# Portable_Lamp_Controller_v2.net
KiCad netlist of a schematic drawn in Altium Designer
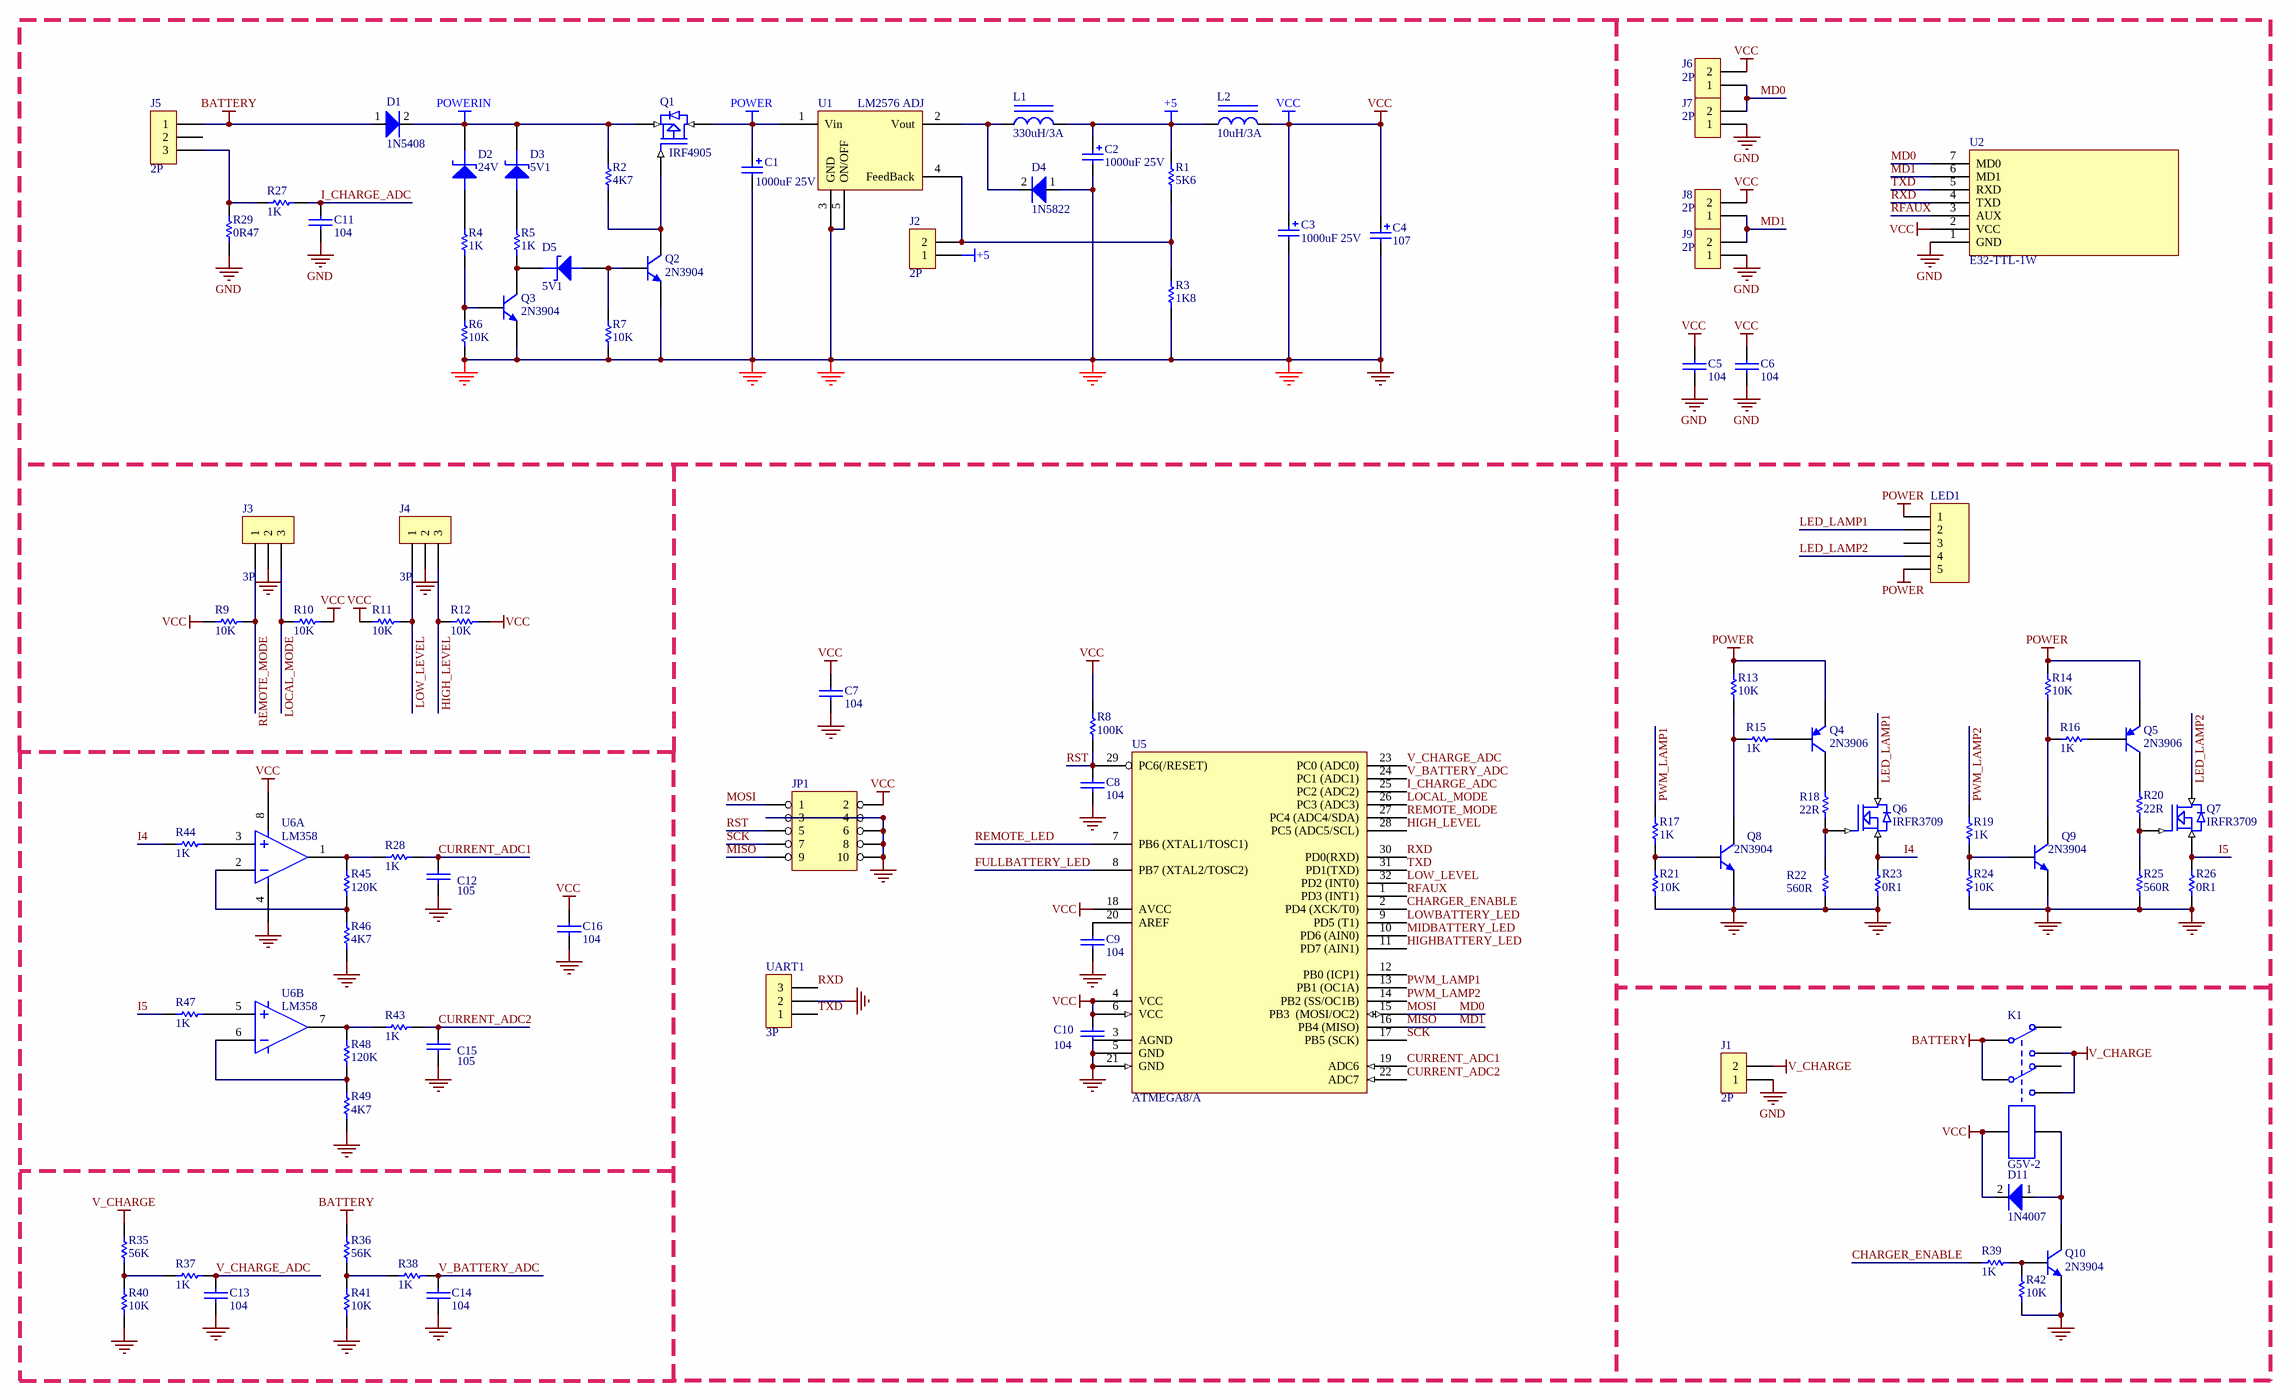
[diagram p0: Portable Lamp Controller v2.SchDoc]

(export (version "E")
  (design (tool "Eeschema 10.0.6"))
  (components
    (comp (ref "C1")
      (value "1000uF 25V")
      (footprint "CAP40x20L")
      (description "Polarized Capacitor (Radial)")
      (fields (field (name "Comment") "Tụ hóa chân cắm1000uF 25V") (field (name "PUBLISHER") "*"))
      (libsource (lib "DnsSchLib") (part "Cap Pol1"))
    )
    (comp (ref "C2")
      (value "1000uF 25V")
      (footprint "CAP40x20L")
      (description "Polarized Capacitor (Radial)")
      (fields (field (name "Comment") "Tụ hóa chân cắm1000uF 25V") (field (name "PUBLISHER") "*"))
      (libsource (lib "DnsSchLib") (part "Cap Pol1"))
    )
    (comp (ref "C3")
      (value "1000uF 25V")
      (footprint "CAP40x20L")
      (description "Polarized Capacitor (Radial)")
      (fields (field (name "Comment") "Tụ hóa chân cắm1000uF 25V") (field (name "PUBLISHER") "*"))
      (libsource (lib "DnsSchLib") (part "Cap Pol1"))
    )
    (comp (ref "C4")
      (value "107")
      (footprint "SMC_E/WA")
      (description "Polarized Capacitor (Radial)")
      (fields (field (name "Comment") "Tụ hóa chân dán107") (field (name "PUBLISHER") "*"))
      (libsource (lib "DnsSchLib") (part "Cap Pol1"))
    )
    (comp (ref "C5")
      (value "104")
      (footprint "0805C")
      (fields (field (name "Comment") "Tụ điện dán 0805104"))
      (libsource (lib "DnsSchLib") (part "CAP"))
    )
    (comp (ref "C6")
      (value "104")
      (footprint "0805C")
      (fields (field (name "Comment") "Tụ điện dán 0805104"))
      (libsource (lib "DnsSchLib") (part "CAP"))
    )
    (comp (ref "C7")
      (value "104")
      (footprint "0805C")
      (fields (field (name "Comment") "Tụ điện dán 0805104"))
      (libsource (lib "DnsSchLib") (part "CAP"))
    )
    (comp (ref "C8")
      (value "104")
      (footprint "0805C")
      (fields (field (name "Comment") "Tụ điện dán 0805104"))
      (libsource (lib "DnsSchLib") (part "CAP"))
    )
    (comp (ref "C9")
      (value "104")
      (footprint "0805C")
      (fields (field (name "Comment") "Tụ điện dán 0805104"))
      (libsource (lib "DnsSchLib") (part "CAP"))
    )
    (comp (ref "C10")
      (value "104")
      (footprint "0805C")
      (fields (field (name "Comment") "Tụ điện dán 0805104"))
      (libsource (lib "DnsSchLib") (part "CAP"))
    )
    (comp (ref "C11")
      (value "104")
      (footprint "0805C")
      (fields (field (name "Comment") "Tụ điện dán 0805104"))
      (libsource (lib "DnsSchLib") (part "CAP"))
    )
    (comp (ref "C12")
      (value "105")
      (footprint "0805C")
      (fields (field (name "Comment") "Tụ điện dán 0805105"))
      (libsource (lib "DnsSchLib") (part "CAP"))
    )
    (comp (ref "C13")
      (value "104")
      (footprint "0805C")
      (fields (field (name "Comment") "Tụ điện dán 0805104"))
      (libsource (lib "DnsSchLib") (part "CAP"))
    )
    (comp (ref "C14")
      (value "104")
      (footprint "0805C")
      (fields (field (name "Comment") "Tụ điện dán 0805104"))
      (libsource (lib "DnsSchLib") (part "CAP"))
    )
    (comp (ref "C15")
      (value "105")
      (footprint "0805C")
      (fields (field (name "Comment") "Tụ điện dán 0805105"))
      (libsource (lib "DnsSchLib") (part "CAP"))
    )
    (comp (ref "C16")
      (value "104")
      (footprint "0805C")
      (fields (field (name "Comment") "Tụ điện dán 0805104"))
      (libsource (lib "DnsSchLib") (part "CAP"))
    )
    (comp (ref "D1")
      (value "1N5408")
      (footprint "1N5408")
      (fields (field (name "Comment") "Diode chỉnh lưu chân cắm 3A1N5408"))
      (libsource (lib "DnsSchLib") (part "DIODE"))
    )
    (comp (ref "D2")
      (value "24V")
      (footprint "1N4148_S")
      (description "Zener Diode")
      (fields (field (name "Comment") "Diode ổn áp zener chân cắm 1W24V"))
      (libsource (lib "DnsSchLib") (part "ZENER2"))
    )
    (comp (ref "D3")
      (value "5V1")
      (footprint "1N4148_S")
      (description "Zener Diode")
      (fields (field (name "Comment") "Diode ổn áp zener chân cắm 1W5V1"))
      (libsource (lib "DnsSchLib") (part "ZENER2"))
    )
    (comp (ref "D4")
      (value "1N5822")
      (footprint "1N5822")
      (fields (field (name "Comment") "Diode xung chân cắm 3A1N5822"))
      (libsource (lib "DnsSchLib") (part "DIODE"))
    )
    (comp (ref "D5")
      (value "5V1")
      (footprint "1N4148_S")
      (description "Zener Diode")
      (fields (field (name "Comment") "Diode ổn áp zener chân cắm 1W5V1"))
      (libsource (lib "DnsSchLib") (part "ZENER2"))
    )
    (comp (ref "D11")
      (value "1N4007")
      (footprint "DIODE1A")
      (fields (field (name "Comment") "Diode chỉnh lưu chân cắm 1A1N4007"))
      (libsource (lib "DnsSchLib") (part "DIODE"))
    )
    (comp (ref "J1")
      (value "2P")
      (footprint "JACK381_2")
      (fields (field (name "Comment") "Giắc xanh loại nằm, 300V/16A - 3.81mm2P"))
      (libsource (lib "DnsSchLib") (part "CON2"))
    )
    (comp (ref "J2")
      (value "2P")
      (footprint "XPAD")
      (fields (field (name "Comment") "Jumper2P"))
      (libsource (lib "DnsSchLib") (part "CON2"))
    )
    (comp (ref "J3")
      (value "3P")
      (footprint "HDR1x3")
      (fields (field (name "Comment") "Jump đực chân thẳng, 2.54mm3P"))
      (libsource (lib "") (part "CON3_1"))
    )
    (comp (ref "J4")
      (value "3P")
      (footprint "HDR1x3")
      (fields (field (name "Comment") "Jump đực chân thẳng, 2.54mm3P"))
      (libsource (lib "") (part "CON3_1"))
    )
    (comp (ref "J5")
      (value "2P")
      (footprint "JACK381_3")
      (fields (field (name "Comment") "Giắc xanh loại nằm, 300V/16A - 3.81mm2P"))
      (libsource (lib "DnsSchLib") (part "CON3"))
    )
    (comp (ref "J6")
      (value "2P")
      (footprint "XPAD")
      (fields (field (name "Comment") "Jumper2P"))
      (libsource (lib "DnsSchLib") (part "CON2"))
    )
    (comp (ref "J7")
      (value "2P")
      (footprint "XPAD")
      (fields (field (name "Comment") "Jumper2P"))
      (libsource (lib "DnsSchLib") (part "CON2"))
    )
    (comp (ref "J8")
      (value "2P")
      (footprint "XPAD")
      (fields (field (name "Comment") "Jumper2P"))
      (libsource (lib "DnsSchLib") (part "CON2"))
    )
    (comp (ref "J9")
      (value "2P")
      (footprint "XPAD")
      (fields (field (name "Comment") "Jumper2P"))
      (libsource (lib "DnsSchLib") (part "CON2"))
    )
    (comp (ref "JP1")
      (value "Jump đực chân thẳng, 2 hàng chân 2.54mm 10P")
      (footprint "HDR2X5")
      (libsource (lib "*") (part "HEADER 5X2"))
    )
    (comp (ref "K1")
      (value "G5V-2")
      (footprint "RELAY")
      (description "Dual-Pole Dual-Throw Relay")
      (fields (field (name "Comment") "Relay OMRON, 8 chân cắmG5V-2") (field (name "PUBLISHER") "*"))
      (libsource (lib "DnsSchLib") (part "Relay-DPDT"))
    )
    (comp (ref "L1")
      (value "330uH/3A")
      (footprint "CAMTRONDUNG")
      (fields (field (name "Comment") "Cuộn cảm chân cắm lõi trụ330uH/3A"))
      (libsource (lib "DnsSchLib") (part "INDUCTORSMALL"))
    )
    (comp (ref "L2")
      (value "10uH/3A")
      (footprint "CAMTRONDUNG")
      (fields (field (name "Comment") "Cuộn cảm chân cắm lõi trụ10uH/3A"))
      (libsource (lib "DnsSchLib") (part "INDUCTORSMALL"))
    )
    (comp (ref "LED1")
      (value "JUMP đực chân thẳng, 2.54mm 5P")
      (footprint "HDR1X5")
      (description "Header, 5-Pin")
      (fields (field (name "PUBLISHER") "Altium Limited"))
      (libsource (lib "Miscellaneous Connectors") (part "Header 5"))
    )
    (comp (ref "Q1")
      (value "IRF4905")
      (footprint "TO220SMD")
      (fields (field (name "Comment") "Transistor trường MOSFET P, chân dán TO-263IRF4905"))
      (libsource (lib "DnsSchLib") (part "MOSFET P"))
    )
    (comp (ref "Q2")
      (value "2N3904")
      (footprint "SOT23S")
      (description "NPN Bipolar Transistor")
      (fields
        (field (name "Comment") "Transistor BJT NPN, chân dán SOT-232N3904")
        (field (name "PUBLISHER") "*")
      )
      (libsource (lib "DnsSchLib") (part "NPN"))
    )
    (comp (ref "Q3")
      (value "2N3904")
      (footprint "SOT23S")
      (description "NPN Bipolar Transistor")
      (fields
        (field (name "Comment") "Transistor BJT NPN, chân dán SOT-232N3904")
        (field (name "PUBLISHER") "*")
      )
      (libsource (lib "DnsSchLib") (part "NPN"))
    )
    (comp (ref "Q4")
      (value "2N3906")
      (footprint "SOT23S")
      (description "PNP Bipolar Transistor")
      (fields
        (field (name "Comment") "Transistor BJT PNP, chân dán SOT-232N3906")
        (field (name "PUBLISHER") "*")
      )
      (libsource (lib "DnsSchLib") (part "PNP"))
    )
    (comp (ref "Q5")
      (value "2N3906")
      (footprint "SOT23S")
      (description "PNP Bipolar Transistor")
      (fields
        (field (name "Comment") "Transistor BJT PNP, chân dán SOT-232N3906")
        (field (name "PUBLISHER") "*")
      )
      (libsource (lib "DnsSchLib") (part "PNP"))
    )
    (comp (ref "Q6")
      (value "IRFR3709")
      (footprint "TO220HSMD")
      (fields (field (name "Comment") "Transistor trường MOSFET N, chân dán TO-263IRFR3709"))
      (libsource (lib "DnsSchLib") (part "MOSFET N"))
    )
    (comp (ref "Q7")
      (value "IRFR3709")
      (footprint "TO220HSMD")
      (fields (field (name "Comment") "Transistor trường MOSFET N, chân dán TO-263IRFR3709"))
      (libsource (lib "DnsSchLib") (part "MOSFET N"))
    )
    (comp (ref "Q8")
      (value "2N3904")
      (footprint "SOT23S")
      (description "NPN Bipolar Transistor")
      (fields
        (field (name "Comment") "Transistor BJT NPN, chân dán SOT-232N3904")
        (field (name "PUBLISHER") "*")
      )
      (libsource (lib "DnsSchLib") (part "NPN"))
    )
    (comp (ref "Q9")
      (value "2N3904")
      (footprint "SOT23S")
      (description "NPN Bipolar Transistor")
      (fields
        (field (name "Comment") "Transistor BJT NPN, chân dán SOT-232N3904")
        (field (name "PUBLISHER") "*")
      )
      (libsource (lib "DnsSchLib") (part "NPN"))
    )
    (comp (ref "Q10")
      (value "2N3904")
      (footprint "SOT23S")
      (description "NPN Bipolar Transistor")
      (fields
        (field (name "Comment") "Transistor BJT NPN, chân dán SOT-232N3904")
        (field (name "PUBLISHER") "*")
      )
      (libsource (lib "DnsSchLib") (part "NPN"))
    )
    (comp (ref "R1")
      (value "5K6")
      (footprint "0805DD")
      (description "Semiconductor Resistor")
      (fields (field (name "Comment") "Điện trở dán 08055K6") (field (name "PUBLISHER") "*"))
      (libsource (lib "DnsSchLib") (part "Res Semi"))
    )
    (comp (ref "R2")
      (value "4K7")
      (footprint "0805DD")
      (description "Semiconductor Resistor")
      (fields (field (name "Comment") "Điện trở dán 08054K7") (field (name "PUBLISHER") "*"))
      (libsource (lib "DnsSchLib") (part "Res Semi"))
    )
    (comp (ref "R3")
      (value "1K8")
      (footprint "0805DD")
      (description "Semiconductor Resistor")
      (fields (field (name "Comment") "Điện trở dán 08051K8") (field (name "PUBLISHER") "*"))
      (libsource (lib "DnsSchLib") (part "Res Semi"))
    )
    (comp (ref "R4")
      (value "1K")
      (footprint "0805DD")
      (description "Semiconductor Resistor")
      (fields (field (name "Comment") "Điện trở dán 08051K") (field (name "PUBLISHER") "*"))
      (libsource (lib "DnsSchLib") (part "Res Semi"))
    )
    (comp (ref "R5")
      (value "1K")
      (footprint "0805DD")
      (description "Semiconductor Resistor")
      (fields (field (name "Comment") "Điện trở dán 08051K") (field (name "PUBLISHER") "*"))
      (libsource (lib "DnsSchLib") (part "Res Semi"))
    )
    (comp (ref "R6")
      (value "10K")
      (footprint "0805DD")
      (description "Semiconductor Resistor")
      (fields (field (name "Comment") "Điện trở dán 080510K") (field (name "PUBLISHER") "*"))
      (libsource (lib "DnsSchLib") (part "Res Semi"))
    )
    (comp (ref "R7")
      (value "10K")
      (footprint "0805DD")
      (description "Semiconductor Resistor")
      (fields (field (name "Comment") "Điện trở dán 080510K") (field (name "PUBLISHER") "*"))
      (libsource (lib "DnsSchLib") (part "Res Semi"))
    )
    (comp (ref "R8")
      (value "100K")
      (footprint "0805DD")
      (description "Semiconductor Resistor")
      (fields (field (name "Comment") "Điện trở dán 0805100K") (field (name "PUBLISHER") "*"))
      (libsource (lib "DnsSchLib") (part "Res Semi"))
    )
    (comp (ref "R9")
      (value "10K")
      (footprint "0805DD")
      (description "Semiconductor Resistor")
      (fields (field (name "Comment") "Điện trở dán 080510K") (field (name "PUBLISHER") "*"))
      (libsource (lib "DnsSchLib") (part "Res Semi"))
    )
    (comp (ref "R10")
      (value "10K")
      (footprint "0805DD")
      (description "Semiconductor Resistor")
      (fields (field (name "Comment") "Điện trở dán 080510K") (field (name "PUBLISHER") "*"))
      (libsource (lib "DnsSchLib") (part "Res Semi"))
    )
    (comp (ref "R11")
      (value "10K")
      (footprint "0805DD")
      (description "Semiconductor Resistor")
      (fields (field (name "Comment") "Điện trở dán 080510K") (field (name "PUBLISHER") "*"))
      (libsource (lib "DnsSchLib") (part "Res Semi"))
    )
    (comp (ref "R12")
      (value "10K")
      (footprint "0805DD")
      (description "Semiconductor Resistor")
      (fields (field (name "Comment") "Điện trở dán 080510K") (field (name "PUBLISHER") "*"))
      (libsource (lib "DnsSchLib") (part "Res Semi"))
    )
    (comp (ref "R13")
      (value "10K")
      (footprint "0805DD")
      (description "Semiconductor Resistor")
      (fields (field (name "Comment") "Điện trở dán 080510K") (field (name "PUBLISHER") "*"))
      (libsource (lib "DnsSchLib") (part "Res Semi"))
    )
    (comp (ref "R14")
      (value "10K")
      (footprint "0805DD")
      (description "Semiconductor Resistor")
      (fields (field (name "Comment") "Điện trở dán 080510K") (field (name "PUBLISHER") "*"))
      (libsource (lib "DnsSchLib") (part "Res Semi"))
    )
    (comp (ref "R15")
      (value "1K")
      (footprint "0805DD")
      (description "Semiconductor Resistor")
      (fields (field (name "Comment") "Điện trở dán 08051K") (field (name "PUBLISHER") "*"))
      (libsource (lib "DnsSchLib") (part "Res Semi"))
    )
    (comp (ref "R16")
      (value "1K")
      (footprint "0805DD")
      (description "Semiconductor Resistor")
      (fields (field (name "Comment") "Điện trở dán 08051K") (field (name "PUBLISHER") "*"))
      (libsource (lib "DnsSchLib") (part "Res Semi"))
    )
    (comp (ref "R17")
      (value "1K")
      (footprint "0805DD")
      (description "Semiconductor Resistor")
      (fields (field (name "Comment") "Điện trở dán 08051K") (field (name "PUBLISHER") "*"))
      (libsource (lib "DnsSchLib") (part "Res Semi"))
    )
    (comp (ref "R18")
      (value "22R")
      (footprint "0805DD")
      (description "Semiconductor Resistor")
      (fields (field (name "Comment") "Điện trở dán 080522R") (field (name "PUBLISHER") "*"))
      (libsource (lib "DnsSchLib") (part "Res Semi"))
    )
    (comp (ref "R19")
      (value "1K")
      (footprint "0805DD")
      (description "Semiconductor Resistor")
      (fields (field (name "Comment") "Điện trở dán 08051K") (field (name "PUBLISHER") "*"))
      (libsource (lib "DnsSchLib") (part "Res Semi"))
    )
    (comp (ref "R20")
      (value "22R")
      (footprint "0805DD")
      (description "Semiconductor Resistor")
      (fields (field (name "Comment") "Điện trở dán 080522R") (field (name "PUBLISHER") "*"))
      (libsource (lib "DnsSchLib") (part "Res Semi"))
    )
    (comp (ref "R21")
      (value "10K")
      (footprint "0805DD")
      (description "Semiconductor Resistor")
      (fields (field (name "Comment") "Điện trở dán 080510K") (field (name "PUBLISHER") "*"))
      (libsource (lib "DnsSchLib") (part "Res Semi"))
    )
    (comp (ref "R22")
      (value "560R")
      (footprint "0805DD")
      (description "Semiconductor Resistor")
      (fields (field (name "Comment") "Điện trở dán 0805560R") (field (name "PUBLISHER") "*"))
      (libsource (lib "DnsSchLib") (part "Res Semi"))
    )
    (comp (ref "R23")
      (value "0R1")
      (footprint "AXIAL0.8S")
      (description "Semiconductor Resistor")
      (fields (field (name "Comment") "Điện trở chân cắm 2W0R1") (field (name "PUBLISHER") "*"))
      (libsource (lib "DnsSchLib") (part "Res Semi"))
    )
    (comp (ref "R24")
      (value "10K")
      (footprint "0805DD")
      (description "Semiconductor Resistor")
      (fields (field (name "Comment") "Điện trở dán 080510K") (field (name "PUBLISHER") "*"))
      (libsource (lib "DnsSchLib") (part "Res Semi"))
    )
    (comp (ref "R25")
      (value "560R")
      (footprint "0805DD")
      (description "Semiconductor Resistor")
      (fields (field (name "Comment") "Điện trở dán 0805560R") (field (name "PUBLISHER") "*"))
      (libsource (lib "DnsSchLib") (part "Res Semi"))
    )
    (comp (ref "R26")
      (value "0R1")
      (footprint "AXIAL0.8S")
      (description "Semiconductor Resistor")
      (fields (field (name "Comment") "Điện trở chân cắm 2W0R1") (field (name "PUBLISHER") "*"))
      (libsource (lib "DnsSchLib") (part "Res Semi"))
    )
    (comp (ref "R27")
      (value "1K")
      (footprint "0805DD")
      (description "Semiconductor Resistor")
      (fields (field (name "Comment") "Điện trở dán 08051K") (field (name "PUBLISHER") "*"))
      (libsource (lib "DnsSchLib") (part "Res Semi"))
    )
    (comp (ref "R28")
      (value "1K")
      (footprint "0805DD")
      (description "Semiconductor Resistor")
      (fields (field (name "Comment") "Điện trở dán 08051K") (field (name "PUBLISHER") "*"))
      (libsource (lib "DnsSchLib") (part "Res Semi"))
    )
    (comp (ref "R29")
      (value "0R47")
      (footprint "AXIAL0.8S")
      (description "Semiconductor Resistor")
      (fields (field (name "Comment") "Điện trở chân cắm 2W0R47") (field (name "PUBLISHER") "*"))
      (libsource (lib "DnsSchLib") (part "Res Semi"))
    )
    (comp (ref "R35")
      (value "56K")
      (footprint "0805DD")
      (description "Semiconductor Resistor")
      (fields (field (name "Comment") "Điện trở dán 0805 1%56K") (field (name "PUBLISHER") "*"))
      (libsource (lib "DnsSchLib") (part "Res Semi"))
    )
    (comp (ref "R36")
      (value "56K")
      (footprint "0805DD")
      (description "Semiconductor Resistor")
      (fields (field (name "Comment") "Điện trở dán 0805 1%56K") (field (name "PUBLISHER") "*"))
      (libsource (lib "DnsSchLib") (part "Res Semi"))
    )
    (comp (ref "R37")
      (value "1K")
      (footprint "0805DD")
      (description "Semiconductor Resistor")
      (fields (field (name "Comment") "Điện trở dán 08051K") (field (name "PUBLISHER") "*"))
      (libsource (lib "DnsSchLib") (part "Res Semi"))
    )
    (comp (ref "R38")
      (value "1K")
      (footprint "0805DD")
      (description "Semiconductor Resistor")
      (fields (field (name "Comment") "Điện trở dán 08051K") (field (name "PUBLISHER") "*"))
      (libsource (lib "DnsSchLib") (part "Res Semi"))
    )
    (comp (ref "R39")
      (value "1K")
      (footprint "0805DD")
      (description "Semiconductor Resistor")
      (fields (field (name "Comment") "Điện trở dán 08051K") (field (name "PUBLISHER") "*"))
      (libsource (lib "DnsSchLib") (part "Res Semi"))
    )
    (comp (ref "R40")
      (value "10K")
      (footprint "0805DD")
      (description "Semiconductor Resistor")
      (fields (field (name "Comment") "Điện trở dán 0805 1%10K") (field (name "PUBLISHER") "*"))
      (libsource (lib "DnsSchLib") (part "Res Semi"))
    )
    (comp (ref "R41")
      (value "10K")
      (footprint "0805DD")
      (description "Semiconductor Resistor")
      (fields (field (name "Comment") "Điện trở dán 0805 1%10K") (field (name "PUBLISHER") "*"))
      (libsource (lib "DnsSchLib") (part "Res Semi"))
    )
    (comp (ref "R42")
      (value "10K")
      (footprint "0805DD")
      (description "Semiconductor Resistor")
      (fields (field (name "Comment") "Điện trở dán 080510K") (field (name "PUBLISHER") "*"))
      (libsource (lib "DnsSchLib") (part "Res Semi"))
    )
    (comp (ref "R43")
      (value "1K")
      (footprint "0805DD")
      (description "Semiconductor Resistor")
      (fields (field (name "Comment") "Điện trở dán 08051K") (field (name "PUBLISHER") "*"))
      (libsource (lib "DnsSchLib") (part "Res Semi"))
    )
    (comp (ref "R44")
      (value "1K")
      (footprint "0805DD")
      (description "Semiconductor Resistor")
      (fields (field (name "Comment") "Điện trở dán 08051K") (field (name "PUBLISHER") "*"))
      (libsource (lib "DnsSchLib") (part "Res Semi"))
    )
    (comp (ref "R45")
      (value "120K")
      (footprint "0805DD")
      (description "Semiconductor Resistor")
      (fields (field (name "Comment") "Điện trở dán 0805 1%120K") (field (name "PUBLISHER") "*"))
      (libsource (lib "DnsSchLib") (part "Res Semi"))
    )
    (comp (ref "R46")
      (value "4K7")
      (footprint "0805DD")
      (description "Semiconductor Resistor")
      (fields (field (name "Comment") "Điện trở dán 0805 1%4K7") (field (name "PUBLISHER") "*"))
      (libsource (lib "DnsSchLib") (part "Res Semi"))
    )
    (comp (ref "R47")
      (value "1K")
      (footprint "0805DD")
      (description "Semiconductor Resistor")
      (fields (field (name "Comment") "Điện trở dán 08051K") (field (name "PUBLISHER") "*"))
      (libsource (lib "DnsSchLib") (part "Res Semi"))
    )
    (comp (ref "R48")
      (value "120K")
      (footprint "0805DD")
      (description "Semiconductor Resistor")
      (fields (field (name "Comment") "Điện trở dán 0805 1%120K") (field (name "PUBLISHER") "*"))
      (libsource (lib "DnsSchLib") (part "Res Semi"))
    )
    (comp (ref "R49")
      (value "4K7")
      (footprint "0805DD")
      (description "Semiconductor Resistor")
      (fields (field (name "Comment") "Điện trở dán 0805 1%4K7") (field (name "PUBLISHER") "*"))
      (libsource (lib "DnsSchLib") (part "Res Semi"))
    )
    (comp (ref "U1")
      (value "LM2576 ADJ")
      (footprint "TO220_5CSMD2")
      (fields (field (name "Comment") "IC chuyển đổi nguồn, chân dánLM2576 ADJ"))
      (libsource (lib "DnsSchLib") (part "LM2576"))
    )
    (comp (ref "U2")
      (value "E32-TTL-1W")
      (footprint "RF_AS32")
      (description "AS32-TTL-1W")
      (fields (field (name "Comment") "Module thu phát không dây RFE32-TTL-1W"))
      (libsource (lib "DnsSchLib") (part "AS32-TTL-1W"))
    )
    (comp (ref "U5")
      (value "ATMEGA8/A")
      (footprint "ATMEGA8")
      (description "TQFP package")
      (fields (field (name "Comment") "Vi điều khiển ATMEL chân dánATMEGA8/A"))
      (libsource (lib "DnsSchLib") (part "ATMEGA8-A"))
    )
    (comp (ref "U6")
      (value "IC khuếch đại thuật toán LM358 chân dán SO-8")
      (footprint "so-8")
      (fields (field (name "NAME") "LM358"))
      (libsource (lib "DnsSchLib") (part "1458"))
    )
    (comp (ref "UART1")
      (value "3P")
      (footprint "HDR1x3")
      (fields (field (name "Comment") "Jump đực chân thẳng, 2.54mm3P"))
      (libsource (lib "") (part "CON3_2"))
    )
  )
  (nets
    (net (code "1") (name "+5") (class "Default")
      (node (ref "C2") (pin "1") (pinfunction "1_1") (pintype "passive"))
      (node (ref "J2") (pin "1") (pinfunction "1_1") (pintype "passive"))
      (node (ref "L1") (pin "2") (pinfunction "2_2") (pintype "passive"))
      (node (ref "L2") (pin "1") (pinfunction "1_1") (pintype "passive"))
      (node (ref "R1") (pin "2") (pinfunction "2_2") (pintype "passive"))
    )
    (net (code "2") (name "/CHARGER_ENABLE") (class "Default")
      (node (ref "R39") (pin "2") (pinfunction "2_2") (pintype "passive"))
      (node (ref "U5") (pin "2") (pinfunction "PD4_(XCK/T0)_2") (pintype "passive"))
    )
    (net (code "3") (name "/CURRENT_ADC1") (class "Default")
      (node (ref "C12") (pin "1") (pinfunction "1_1") (pintype "passive"))
      (node (ref "R28") (pin "1") (pinfunction "1_1") (pintype "passive"))
      (node (ref "U5") (pin "19") (pinfunction "ADC6_19") (pintype "input"))
    )
    (net (code "4") (name "/CURRENT_ADC2") (class "Default")
      (node (ref "C15") (pin "1") (pinfunction "1_1") (pintype "passive"))
      (node (ref "R43") (pin "1") (pinfunction "1_1") (pintype "passive"))
      (node (ref "U5") (pin "22") (pinfunction "ADC7_22") (pintype "input"))
    )
    (net (code "5") (name "/FULLBATTERY_LED") (class "Default")
      (node (ref "U5") (pin "8") (pinfunction "PB7_(XTAL2/TOSC2)_8") (pintype "passive"))
    )
    (net (code "6") (name "/HIGHBATTERY_LED") (class "Default")
      (node (ref "U5") (pin "11") (pinfunction "PD7_(AIN1)_11") (pintype "passive"))
    )
    (net (code "7") (name "/HIGH_LEVEL") (class "Default")
      (node (ref "J4") (pin "3") (pinfunction "3_3") (pintype "passive"))
      (node (ref "R12") (pin "2") (pinfunction "2_2") (pintype "passive"))
      (node (ref "U5") (pin "28") (pinfunction "PC5_(ADC5/SCL)_28") (pintype "passive"))
    )
    (net (code "8") (name "/I4") (class "Default")
      (node (ref "Q6") (pin "3") (pinfunction "S_3") (pintype "input"))
      (node (ref "R23") (pin "2") (pinfunction "2_2") (pintype "passive"))
      (node (ref "R44") (pin "1") (pinfunction "1_1") (pintype "passive"))
    )
    (net (code "9") (name "/I5") (class "Default")
      (node (ref "Q7") (pin "3") (pinfunction "S_3") (pintype "input"))
      (node (ref "R26") (pin "2") (pinfunction "2_2") (pintype "passive"))
      (node (ref "R47") (pin "1") (pinfunction "1_1") (pintype "passive"))
    )
    (net (code "10") (name "/I_CHARGE_ADC") (class "Default")
      (node (ref "C11") (pin "1") (pinfunction "1_1") (pintype "passive"))
      (node (ref "R27") (pin "2") (pinfunction "2_2") (pintype "passive"))
      (node (ref "U5") (pin "25") (pinfunction "PC2_(ADC2)_25") (pintype "passive"))
    )
    (net (code "11") (name "/LED_LAMP1") (class "Default")
      (node (ref "LED1") (pin "2") (pinfunction "2_2") (pintype "passive"))
      (node (ref "Q6") (pin "2") (pinfunction "D_2") (pintype "input"))
    )
    (net (code "12") (name "/LED_LAMP2") (class "Default")
      (node (ref "LED1") (pin "4") (pinfunction "4_4") (pintype "passive"))
      (node (ref "Q7") (pin "2") (pinfunction "D_2") (pintype "input"))
    )
    (net (code "13") (name "/LOCAL_MODE") (class "Default")
      (node (ref "J3") (pin "3") (pinfunction "3_3") (pintype "passive"))
      (node (ref "R10") (pin "1") (pinfunction "1_1") (pintype "passive"))
      (node (ref "U5") (pin "26") (pinfunction "PC3_(ADC3)_26") (pintype "passive"))
    )
    (net (code "14") (name "/LOWBATTERY_LED") (class "Default")
      (node (ref "U5") (pin "9") (pinfunction "PD5_(T1)_9") (pintype "passive"))
    )
    (net (code "15") (name "/LOW_LEVEL") (class "Default")
      (node (ref "J4") (pin "1") (pinfunction "1_1") (pintype "passive"))
      (node (ref "R11") (pin "2") (pinfunction "2_2") (pintype "passive"))
      (node (ref "U5") (pin "32") (pinfunction "PD2_(INT0)_32") (pintype "passive"))
    )
    (net (code "16") (name "/MD0") (class "Default")
      (node (ref "J6") (pin "1") (pinfunction "1_1") (pintype "passive"))
      (node (ref "J7") (pin "2") (pinfunction "2_2") (pintype "passive"))
      (node (ref "JP1") (pin "1") (pinfunction "1_1") (pintype "passive"))
      (node (ref "U2") (pin "7") (pinfunction "MD0_7") (pintype "passive"))
      (node (ref "U5") (pin "15") (pinfunction "PB3__(MOSI/OC2)_15") (pintype "bidirectional"))
    )
    (net (code "17") (name "/MD1") (class "Default")
      (node (ref "J8") (pin "1") (pinfunction "1_1") (pintype "passive"))
      (node (ref "J9") (pin "2") (pinfunction "2_2") (pintype "passive"))
      (node (ref "JP1") (pin "9") (pinfunction "9_9") (pintype "passive"))
      (node (ref "U2") (pin "6") (pinfunction "MD1_6") (pintype "passive"))
      (node (ref "U5") (pin "16") (pinfunction "PB4_(MISO)_16") (pintype "passive"))
    )
    (net (code "18") (name "/MIDBATTERY_LED") (class "Default")
      (node (ref "U5") (pin "10") (pinfunction "PD6_(AIN0)_10") (pintype "passive"))
    )
    (net (code "19") (name "/PWM_LAMP1") (class "Default")
      (node (ref "R17") (pin "1") (pinfunction "1_1") (pintype "passive"))
      (node (ref "U5") (pin "13") (pinfunction "PB1_(OC1A)_13") (pintype "passive"))
    )
    (net (code "20") (name "/PWM_LAMP2") (class "Default")
      (node (ref "R19") (pin "1") (pinfunction "1_1") (pintype "passive"))
      (node (ref "U5") (pin "14") (pinfunction "PB2_(SS/OC1B)_14") (pintype "passive"))
    )
    (net (code "21") (name "/REMOTE_LED") (class "Default")
      (node (ref "U5") (pin "7") (pinfunction "PB6_(XTAL1/TOSC1)_7") (pintype "passive"))
    )
    (net (code "22") (name "/REMOTE_MODE") (class "Default")
      (node (ref "J3") (pin "1") (pinfunction "1_1") (pintype "passive"))
      (node (ref "R9") (pin "1") (pinfunction "1_1") (pintype "passive"))
      (node (ref "U5") (pin "27") (pinfunction "PC4_(ADC4/SDA)_27") (pintype "passive"))
    )
    (net (code "23") (name "/RFAUX") (class "Default")
      (node (ref "U2") (pin "3") (pinfunction "AUX_3") (pintype "passive"))
      (node (ref "U5") (pin "1") (pinfunction "PD3_(INT1)_1") (pintype "passive"))
    )
    (net (code "24") (name "/RST") (class "Default")
      (node (ref "C8") (pin "1") (pinfunction "1_1") (pintype "passive"))
      (node (ref "JP1") (pin "5") (pinfunction "5_5") (pintype "passive"))
      (node (ref "R8") (pin "1") (pinfunction "1_1") (pintype "passive"))
      (node (ref "U5") (pin "29") (pinfunction "PC6(/RESET)_29") (pintype "passive"))
    )
    (net (code "25") (name "/RXD") (class "Default")
      (node (ref "U2") (pin "4") (pinfunction "TXD_4") (pintype "passive"))
      (node (ref "U5") (pin "30") (pinfunction "PD0(RXD)_30") (pintype "passive"))
      (node (ref "UART1") (pin "3") (pinfunction "3_3") (pintype "passive"))
    )
    (net (code "26") (name "/SCK") (class "Default")
      (node (ref "JP1") (pin "7") (pinfunction "7_7") (pintype "passive"))
      (node (ref "U5") (pin "17") (pinfunction "PB5_(SCK)_17") (pintype "passive"))
    )
    (net (code "27") (name "/TXD") (class "Default")
      (node (ref "U2") (pin "5") (pinfunction "RXD_5") (pintype "passive"))
      (node (ref "U5") (pin "31") (pinfunction "PD1(TXD)_31") (pintype "passive"))
      (node (ref "UART1") (pin "1") (pinfunction "1_1") (pintype "passive"))
    )
    (net (code "28") (name "/V_BATTERY_ADC") (class "Default")
      (node (ref "C14") (pin "1") (pinfunction "1_1") (pintype "passive"))
      (node (ref "R38") (pin "2") (pinfunction "2_2") (pintype "passive"))
      (node (ref "U5") (pin "24") (pinfunction "PC1_(ADC1)_24") (pintype "passive"))
    )
    (net (code "29") (name "/V_CHARGE_ADC") (class "Default")
      (node (ref "C13") (pin "1") (pinfunction "1_1") (pintype "passive"))
      (node (ref "R37") (pin "2") (pinfunction "2_2") (pintype "passive"))
      (node (ref "U5") (pin "23") (pinfunction "PC0_(ADC0)_23") (pintype "passive"))
    )
    (net (code "30") (name "BATTERY") (class "Default")
      (node (ref "D1") (pin "1") (pinfunction "A_1") (pintype "passive"))
      (node (ref "J5") (pin "1") (pinfunction "1_1") (pintype "passive"))
      (node (ref "K1") (pin "1") (pinfunction "1_1") (pintype "passive"))
      (node (ref "K1") (pin "4") (pinfunction "4_4") (pintype "passive"))
      (node (ref "R36") (pin "2") (pinfunction "2_2") (pintype "passive"))
    )
    (net (code "31") (name "GND") (class "Default")
      (node (ref "C1") (pin "2") (pinfunction "2_2") (pintype "passive"))
      (node (ref "C10") (pin "1") (pinfunction "1_1") (pintype "passive"))
      (node (ref "C11") (pin "2") (pinfunction "2_2") (pintype "passive"))
      (node (ref "C12") (pin "2") (pinfunction "2_2") (pintype "passive"))
      (node (ref "C13") (pin "2") (pinfunction "2_2") (pintype "passive"))
      (node (ref "C14") (pin "2") (pinfunction "2_2") (pintype "passive"))
      (node (ref "C15") (pin "2") (pinfunction "2_2") (pintype "passive"))
      (node (ref "C16") (pin "1") (pinfunction "1_1") (pintype "passive"))
      (node (ref "C2") (pin "2") (pinfunction "2_2") (pintype "passive"))
      (node (ref "C3") (pin "2") (pinfunction "2_2") (pintype "passive"))
      (node (ref "C4") (pin "2") (pinfunction "2_2") (pintype "passive"))
      (node (ref "C5") (pin "2") (pinfunction "2_2") (pintype "passive"))
      (node (ref "C6") (pin "1") (pinfunction "1_1") (pintype "passive"))
      (node (ref "C7") (pin "1") (pinfunction "1_1") (pintype "passive"))
      (node (ref "C8") (pin "2") (pinfunction "2_2") (pintype "passive"))
      (node (ref "C9") (pin "1") (pinfunction "1_1") (pintype "passive"))
      (node (ref "D4") (pin "1") (pinfunction "A_1") (pintype "passive"))
      (node (ref "J1") (pin "1") (pinfunction "1_1") (pintype "passive"))
      (node (ref "J3") (pin "2") (pinfunction "2_2") (pintype "passive"))
      (node (ref "J4") (pin "2") (pinfunction "2_2") (pintype "passive"))
      (node (ref "J7") (pin "1") (pinfunction "1_1") (pintype "passive"))
      (node (ref "J9") (pin "1") (pinfunction "1_1") (pintype "passive"))
      (node (ref "JP1") (pin "10") (pinfunction "10_10") (pintype "passive"))
      (node (ref "JP1") (pin "3") (pinfunction "3_3") (pintype "passive"))
      (node (ref "JP1") (pin "4") (pinfunction "4_4") (pintype "passive"))
      (node (ref "JP1") (pin "6") (pinfunction "6_6") (pintype "passive"))
      (node (ref "JP1") (pin "8") (pinfunction "8_8") (pintype "passive"))
      (node (ref "Q10") (pin "3") (pinfunction "E_3") (pintype "passive"))
      (node (ref "Q2") (pin "3") (pinfunction "E_3") (pintype "passive"))
      (node (ref "Q3") (pin "3") (pinfunction "E_3") (pintype "passive"))
      (node (ref "Q8") (pin "3") (pinfunction "E_3") (pintype "passive"))
      (node (ref "Q9") (pin "3") (pinfunction "E_3") (pintype "passive"))
      (node (ref "R21") (pin "1") (pinfunction "1_1") (pintype "passive"))
      (node (ref "R22") (pin "2") (pinfunction "2_2") (pintype "passive"))
      (node (ref "R23") (pin "1") (pinfunction "1_1") (pintype "passive"))
      (node (ref "R24") (pin "1") (pinfunction "1_1") (pintype "passive"))
      (node (ref "R25") (pin "2") (pinfunction "2_2") (pintype "passive"))
      (node (ref "R26") (pin "1") (pinfunction "1_1") (pintype "passive"))
      (node (ref "R29") (pin "1") (pinfunction "1_1") (pintype "passive"))
      (node (ref "R3") (pin "1") (pinfunction "1_1") (pintype "passive"))
      (node (ref "R40") (pin "1") (pinfunction "1_1") (pintype "passive"))
      (node (ref "R41") (pin "1") (pinfunction "1_1") (pintype "passive"))
      (node (ref "R42") (pin "1") (pinfunction "1_1") (pintype "passive"))
      (node (ref "R46") (pin "1") (pinfunction "1_1") (pintype "passive"))
      (node (ref "R49") (pin "2") (pinfunction "2_2") (pintype "passive"))
      (node (ref "R6") (pin "1") (pinfunction "1_1") (pintype "passive"))
      (node (ref "R7") (pin "1") (pinfunction "1_1") (pintype "passive"))
      (node (ref "U1") (pin "3") (pinfunction "GND_3") (pintype "passive"))
      (node (ref "U1") (pin "5") (pinfunction "ON/OFF_5") (pintype "passive"))
      (node (ref "U2") (pin "1") (pinfunction "GND_1") (pintype "passive"))
      (node (ref "U5") (pin "21") (pinfunction "GND_21") (pintype "input"))
      (node (ref "U5") (pin "3") (pinfunction "AGND_3") (pintype "passive"))
      (node (ref "U5") (pin "5") (pinfunction "GND_5") (pintype "passive"))
      (node (ref "U6") (pin "4") (pintype "passive"))
      (node (ref "UART1") (pin "2") (pinfunction "2_2") (pintype "passive"))
    )
    (net (code "32") (name "Net-(D2-A)") (class "Default")
      (node (ref "D2") (pin "1") (pinfunction "A_1") (pintype "passive"))
      (node (ref "R4") (pin "2") (pinfunction "2_2") (pintype "passive"))
    )
    (net (code "33") (name "Net-(D3-A)") (class "Default")
      (node (ref "D3") (pin "1") (pinfunction "A_1") (pintype "passive"))
      (node (ref "R5") (pin "2") (pinfunction "2_2") (pintype "passive"))
    )
    (net (code "34") (name "Net-(D4-K)") (class "Default")
      (node (ref "D4") (pin "2") (pinfunction "K_2") (pintype "passive"))
      (node (ref "L1") (pin "1") (pinfunction "1_1") (pintype "passive"))
      (node (ref "U1") (pin "2") (pinfunction "Vout_2") (pintype "passive"))
    )
    (net (code "35") (name "Net-(D5-A)") (class "Default")
      (node (ref "D5") (pin "1") (pinfunction "A_1") (pintype "passive"))
      (node (ref "Q2") (pin "1") (pinfunction "B_1") (pintype "passive"))
      (node (ref "R7") (pin "2") (pinfunction "2_2") (pintype "passive"))
    )
    (net (code "36") (name "Net-(D5-K)") (class "Default")
      (node (ref "D5") (pin "2") (pinfunction "K_2") (pintype "passive"))
      (node (ref "Q3") (pin "2") (pinfunction "C_2") (pintype "passive"))
      (node (ref "R5") (pin "1") (pinfunction "1_1") (pintype "passive"))
    )
    (net (code "37") (name "Net-(D11-A)") (class "Default")
      (node (ref "D11") (pin "1") (pinfunction "A_1") (pintype "passive"))
      (node (ref "K1") (pin "8") (pinfunction "8_8") (pintype "passive"))
      (node (ref "Q10") (pin "2") (pinfunction "C_2") (pintype "passive"))
    )
    (net (code "38") (name "Net-(J5-Pad3)") (class "Default")
      (node (ref "J5") (pin "3") (pinfunction "3_3") (pintype "passive"))
      (node (ref "R27") (pin "1") (pinfunction "1_1") (pintype "passive"))
      (node (ref "R29") (pin "2") (pinfunction "2_2") (pintype "passive"))
    )
    (net (code "39") (name "Net-(Q1-G)") (class "Default")
      (node (ref "Q1") (pin "1") (pinfunction "G_1") (pintype "input"))
      (node (ref "Q2") (pin "2") (pinfunction "C_2") (pintype "passive"))
      (node (ref "R2") (pin "1") (pinfunction "1_1") (pintype "passive"))
    )
    (net (code "40") (name "Net-(Q3-B)") (class "Default")
      (node (ref "Q3") (pin "1") (pinfunction "B_1") (pintype "passive"))
      (node (ref "R4") (pin "1") (pinfunction "1_1") (pintype "passive"))
      (node (ref "R6") (pin "2") (pinfunction "2_2") (pintype "passive"))
    )
    (net (code "41") (name "Net-(Q4-B)") (class "Default")
      (node (ref "Q4") (pin "1") (pinfunction "B_1") (pintype "passive"))
      (node (ref "R15") (pin "1") (pinfunction "1_1") (pintype "passive"))
    )
    (net (code "42") (name "Net-(Q4-C)") (class "Default")
      (node (ref "Q4") (pin "2") (pinfunction "C_2") (pintype "passive"))
      (node (ref "R18") (pin "1") (pinfunction "1_1") (pintype "passive"))
    )
    (net (code "43") (name "Net-(Q5-B)") (class "Default")
      (node (ref "Q5") (pin "1") (pinfunction "B_1") (pintype "passive"))
      (node (ref "R16") (pin "1") (pinfunction "1_1") (pintype "passive"))
    )
    (net (code "44") (name "Net-(Q5-C)") (class "Default")
      (node (ref "Q5") (pin "2") (pinfunction "C_2") (pintype "passive"))
      (node (ref "R20") (pin "1") (pinfunction "1_1") (pintype "passive"))
    )
    (net (code "45") (name "Net-(Q6-G)") (class "Default")
      (node (ref "Q6") (pin "1") (pinfunction "G_1") (pintype "input"))
      (node (ref "R18") (pin "2") (pinfunction "2_2") (pintype "passive"))
      (node (ref "R22") (pin "1") (pinfunction "1_1") (pintype "passive"))
    )
    (net (code "46") (name "Net-(Q7-G)") (class "Default")
      (node (ref "Q7") (pin "1") (pinfunction "G_1") (pintype "input"))
      (node (ref "R20") (pin "2") (pinfunction "2_2") (pintype "passive"))
      (node (ref "R25") (pin "1") (pinfunction "1_1") (pintype "passive"))
    )
    (net (code "47") (name "Net-(Q8-B)") (class "Default")
      (node (ref "Q8") (pin "1") (pinfunction "B_1") (pintype "passive"))
      (node (ref "R17") (pin "2") (pinfunction "2_2") (pintype "passive"))
      (node (ref "R21") (pin "2") (pinfunction "2_2") (pintype "passive"))
    )
    (net (code "48") (name "Net-(Q8-C)") (class "Default")
      (node (ref "Q8") (pin "2") (pinfunction "C_2") (pintype "passive"))
      (node (ref "R13") (pin "1") (pinfunction "1_1") (pintype "passive"))
      (node (ref "R15") (pin "2") (pinfunction "2_2") (pintype "passive"))
    )
    (net (code "49") (name "Net-(Q9-B)") (class "Default")
      (node (ref "Q9") (pin "1") (pinfunction "B_1") (pintype "passive"))
      (node (ref "R19") (pin "2") (pinfunction "2_2") (pintype "passive"))
      (node (ref "R24") (pin "2") (pinfunction "2_2") (pintype "passive"))
    )
    (net (code "50") (name "Net-(Q9-C)") (class "Default")
      (node (ref "Q9") (pin "2") (pinfunction "C_2") (pintype "passive"))
      (node (ref "R14") (pin "1") (pinfunction "1_1") (pintype "passive"))
      (node (ref "R16") (pin "2") (pinfunction "2_2") (pintype "passive"))
    )
    (net (code "51") (name "Net-(Q10-B)") (class "Default")
      (node (ref "Q10") (pin "1") (pinfunction "B_1") (pintype "passive"))
      (node (ref "R39") (pin "1") (pinfunction "1_1") (pintype "passive"))
      (node (ref "R42") (pin "2") (pinfunction "2_2") (pintype "passive"))
    )
    (net (code "52") (name "Net-(R28-Pad2)") (class "Default")
      (node (ref "R28") (pin "2") (pinfunction "2_2") (pintype "passive"))
      (node (ref "R45") (pin "2") (pinfunction "2_2") (pintype "passive"))
      (node (ref "U6") (pin "1") (pintype "passive"))
    )
    (net (code "53") (name "Net-(R35-Pad1)") (class "Default")
      (node (ref "R35") (pin "1") (pinfunction "1_1") (pintype "passive"))
      (node (ref "R37") (pin "1") (pinfunction "1_1") (pintype "passive"))
      (node (ref "R40") (pin "2") (pinfunction "2_2") (pintype "passive"))
    )
    (net (code "54") (name "Net-(R36-Pad1)") (class "Default")
      (node (ref "R36") (pin "1") (pinfunction "1_1") (pintype "passive"))
      (node (ref "R38") (pin "1") (pinfunction "1_1") (pintype "passive"))
      (node (ref "R41") (pin "2") (pinfunction "2_2") (pintype "passive"))
    )
    (net (code "55") (name "Net-(R43-Pad2)") (class "Default")
      (node (ref "R43") (pin "2") (pinfunction "2_2") (pintype "passive"))
      (node (ref "R48") (pin "2") (pinfunction "2_2") (pintype "passive"))
      (node (ref "U6") (pin "7") (pintype "passive"))
    )
    (net (code "56") (name "Net-(R44-Pad2)") (class "Default")
      (node (ref "R44") (pin "2") (pinfunction "2_2") (pintype "passive"))
      (node (ref "U6") (pin "3") (pintype "passive"))
    )
    (net (code "57") (name "Net-(R45-Pad1)") (class "Default")
      (node (ref "R45") (pin "1") (pinfunction "1_1") (pintype "passive"))
      (node (ref "R46") (pin "2") (pinfunction "2_2") (pintype "passive"))
      (node (ref "U6") (pin "2") (pintype "passive"))
    )
    (net (code "58") (name "Net-(R47-Pad2)") (class "Default")
      (node (ref "R47") (pin "2") (pinfunction "2_2") (pintype "passive"))
      (node (ref "U6") (pin "5") (pintype "passive"))
    )
    (net (code "59") (name "Net-(R48-Pad1)") (class "Default")
      (node (ref "R48") (pin "1") (pinfunction "1_1") (pintype "passive"))
      (node (ref "R49") (pin "1") (pinfunction "1_1") (pintype "passive"))
      (node (ref "U6") (pin "6") (pintype "passive"))
    )
    (net (code "60") (name "Net-(U1-FeedBack)") (class "Default")
      (node (ref "J2") (pin "2") (pinfunction "2_2") (pintype "passive"))
      (node (ref "R1") (pin "1") (pinfunction "1_1") (pintype "passive"))
      (node (ref "R3") (pin "2") (pinfunction "2_2") (pintype "passive"))
      (node (ref "U1") (pin "4") (pinfunction "FeedBack_4") (pintype "passive"))
    )
    (net (code "61") (name "Net-(U5-AREF)") (class "Default")
      (node (ref "C9") (pin "2") (pinfunction "2_2") (pintype "passive"))
      (node (ref "U5") (pin "20") (pinfunction "AREF_20") (pintype "passive"))
    )
    (net (code "62") (name "POWER") (class "Default")
      (node (ref "C1") (pin "1") (pinfunction "1_1") (pintype "passive"))
      (node (ref "LED1") (pin "1") (pinfunction "1_1") (pintype "passive"))
      (node (ref "LED1") (pin "5") (pinfunction "5_5") (pintype "passive"))
      (node (ref "Q1") (pin "2") (pinfunction "D_2") (pintype "input"))
      (node (ref "Q4") (pin "3") (pinfunction "E_3") (pintype "passive"))
      (node (ref "Q5") (pin "3") (pinfunction "E_3") (pintype "passive"))
      (node (ref "R13") (pin "2") (pinfunction "2_2") (pintype "passive"))
      (node (ref "R14") (pin "2") (pinfunction "2_2") (pintype "passive"))
      (node (ref "U1") (pin "1") (pinfunction "Vin_1") (pintype "passive"))
    )
    (net (code "63") (name "POWERIN") (class "Default")
      (node (ref "D1") (pin "2") (pinfunction "K_2") (pintype "passive"))
      (node (ref "D2") (pin "2") (pinfunction "K_2") (pintype "passive"))
      (node (ref "D3") (pin "2") (pinfunction "K_2") (pintype "passive"))
      (node (ref "Q1") (pin "3") (pinfunction "S_3") (pintype "input"))
      (node (ref "R2") (pin "2") (pinfunction "2_2") (pintype "passive"))
    )
    (net (code "64") (name "VCC") (class "Default")
      (node (ref "C10") (pin "2") (pinfunction "2_2") (pintype "passive"))
      (node (ref "C16") (pin "2") (pinfunction "2_2") (pintype "passive"))
      (node (ref "C3") (pin "1") (pinfunction "1_1") (pintype "passive"))
      (node (ref "C4") (pin "1") (pinfunction "1_1") (pintype "passive"))
      (node (ref "C5") (pin "1") (pinfunction "1_1") (pintype "passive"))
      (node (ref "C6") (pin "2") (pinfunction "2_2") (pintype "passive"))
      (node (ref "C7") (pin "2") (pinfunction "2_2") (pintype "passive"))
      (node (ref "D11") (pin "2") (pinfunction "K_2") (pintype "passive"))
      (node (ref "J6") (pin "2") (pinfunction "2_2") (pintype "passive"))
      (node (ref "J8") (pin "2") (pinfunction "2_2") (pintype "passive"))
      (node (ref "JP1") (pin "2") (pinfunction "2_2") (pintype "passive"))
      (node (ref "K1") (pin "7") (pinfunction "7_7") (pintype "passive"))
      (node (ref "L2") (pin "2") (pinfunction "2_2") (pintype "passive"))
      (node (ref "R10") (pin "2") (pinfunction "2_2") (pintype "passive"))
      (node (ref "R11") (pin "1") (pinfunction "1_1") (pintype "passive"))
      (node (ref "R12") (pin "1") (pinfunction "1_1") (pintype "passive"))
      (node (ref "R8") (pin "2") (pinfunction "2_2") (pintype "passive"))
      (node (ref "R9") (pin "2") (pinfunction "2_2") (pintype "passive"))
      (node (ref "U2") (pin "2") (pinfunction "VCC_2") (pintype "passive"))
      (node (ref "U5") (pin "18") (pinfunction "AVCC_18") (pintype "passive"))
      (node (ref "U5") (pin "4") (pinfunction "VCC_4") (pintype "passive"))
      (node (ref "U5") (pin "6") (pinfunction "VCC_6") (pintype "input"))
      (node (ref "U6") (pin "8") (pintype "passive"))
    )
    (net (code "65") (name "V_CHARGE") (class "Default")
      (node (ref "J1") (pin "2") (pinfunction "2_2") (pintype "passive"))
      (node (ref "K1") (pin "3") (pinfunction "3_3") (pintype "passive"))
      (node (ref "K1") (pin "6") (pinfunction "6_6") (pintype "passive"))
      (node (ref "R35") (pin "2") (pinfunction "2_2") (pintype "passive"))
    )
    (net (code "66") (name "unconnected-(J5-Pad2)") (class "Default")
      (node (ref "J5") (pin "2") (pinfunction "2_2") (pintype "passive"))
    )
    (net (code "67") (name "unconnected-(K1-Pad2)") (class "Default")
      (node (ref "K1") (pin "2") (pinfunction "2_2") (pintype "passive"))
    )
    (net (code "68") (name "unconnected-(K1-Pad5)") (class "Default")
      (node (ref "K1") (pin "5") (pinfunction "5_5") (pintype "passive"))
    )
    (net (code "69") (name "unconnected-(LED1-Pad3)") (class "Default")
      (node (ref "LED1") (pin "3") (pinfunction "3_3") (pintype "passive"))
    )
    (net (code "70") (name "unconnected-(U5-PB0_(ICP1)-Pad12)") (class "Default")
      (node (ref "U5") (pin "12") (pinfunction "PB0_(ICP1)_12") (pintype "passive"))
    )
  )
)
